# RFD900X_Holder.net
KiCad netlist of a schematic drawn in Altium Designer
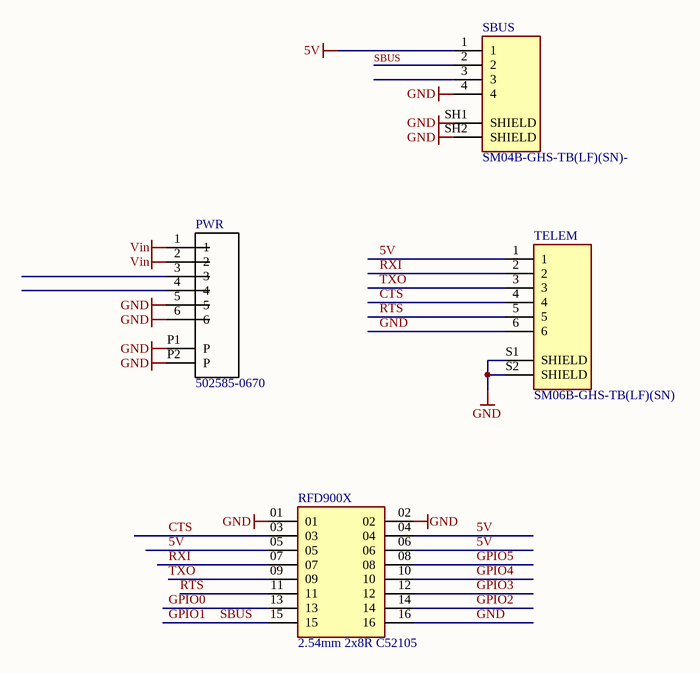
[diagram p0: RFD900X Holder.SchDoc]

(export (version "E")
  (design (tool "Eeschema 10.0.6"))
  (components
    (comp (ref "PWR")
      (value "502585-0670")
      (footprint "MOLEX_502585-0670")
      (fields (field (name "MF") "Molex"))
      (libsource (lib "lib") (part "502585-0670"))
    )
    (comp (ref "RFD900X")
      (value "2.54mm 2x8R C52105")
      (footprint "2.54mm 2x8R")
      (fields (field (name "MF") "BOOMELE") (field (name "MP") "C52105"))
      (libsource (lib "lib") (part "2.54mm 2x8R C52105"))
    )
    (comp (ref "SBUS")
      (value "SM04B-GHS-TB(LF)(SN)-")
      (footprint "JST_SM04B-GHS-TB(LF)(SN)-")
      (description "Connector Header Surface Mount, Right Angle 4 position 0.049 _1.25mm_")
      (fields (field (name "MP") "SM04B-GHS-TB(LF)(SN)") (field (name "MF") "JST Sales"))
      (libsource (lib "lib") (part "SM04B-GHS-TB(LF)(SN)-"))
    )
    (comp (ref "TELEM")
      (value "SM06B-GHS-TB(LF)(SN)")
      (footprint "JST_SM06B-GHS-TB(LF)(SN)")
      (description "Connector Header Surface Mount, Right Angle 6 position 0.049\" (1.25mm)")
      (fields (field (name "MP") "SM06B-GHS-TB_LF__SN_") (field (name "MF") "JST Sales"))
      (libsource (lib "lib") (part "SM06B-GHS-TB(LF)(SN)"))
    )
  )
  (nets
    (net (code "1") (name "/CTS") (class "Default")
      (node (ref "RFD900X") (pin "03") (pinfunction "03_03") (pintype "passive"))
      (node (ref "TELEM") (pin "4") (pinfunction "4_4") (pintype "passive"))
    )
    (net (code "2") (name "/GPIO0") (class "Default")
      (node (ref "RFD900X") (pin "13") (pinfunction "13_13") (pintype "passive"))
    )
    (net (code "3") (name "/GPIO1") (class "Default")
      (node (ref "RFD900X") (pin "15") (pinfunction "15_15") (pintype "passive"))
      (node (ref "SBUS") (pin "2") (pinfunction "2_2") (pintype "passive"))
    )
    (net (code "4") (name "/GPIO2") (class "Default")
      (node (ref "RFD900X") (pin "14") (pinfunction "14_14") (pintype "passive"))
    )
    (net (code "5") (name "/GPIO3") (class "Default")
      (node (ref "RFD900X") (pin "12") (pinfunction "12_12") (pintype "passive"))
    )
    (net (code "6") (name "/GPIO4") (class "Default")
      (node (ref "RFD900X") (pin "10") (pinfunction "10_10") (pintype "passive"))
    )
    (net (code "7") (name "/GPIO5") (class "Default")
      (node (ref "RFD900X") (pin "08") (pinfunction "08_08") (pintype "passive"))
    )
    (net (code "8") (name "/RTS") (class "Default")
      (node (ref "RFD900X") (pin "11") (pinfunction "11_11") (pintype "passive"))
      (node (ref "TELEM") (pin "5") (pinfunction "5_5") (pintype "passive"))
    )
    (net (code "9") (name "/RXI") (class "Default")
      (node (ref "RFD900X") (pin "07") (pinfunction "07_07") (pintype "passive"))
      (node (ref "TELEM") (pin "2") (pinfunction "2_2") (pintype "passive"))
    )
    (net (code "10") (name "/TXO") (class "Default")
      (node (ref "RFD900X") (pin "09") (pinfunction "09_09") (pintype "passive"))
      (node (ref "TELEM") (pin "3") (pinfunction "3_3") (pintype "passive"))
    )
    (net (code "11") (name "5V") (class "Default")
      (node (ref "RFD900X") (pin "04") (pinfunction "04_04") (pintype "passive"))
      (node (ref "RFD900X") (pin "05") (pinfunction "05_05") (pintype "passive"))
      (node (ref "RFD900X") (pin "06") (pinfunction "06_06") (pintype "passive"))
      (node (ref "SBUS") (pin "1") (pinfunction "1_1") (pintype "passive"))
      (node (ref "TELEM") (pin "1") (pinfunction "1_1") (pintype "passive"))
    )
    (net (code "12") (name "GND") (class "Default")
      (node (ref "PWR") (pin "5") (pinfunction "5_5") (pintype "passive"))
      (node (ref "PWR") (pin "6") (pinfunction "6_6") (pintype "passive"))
      (node (ref "PWR") (pin "P1") (pinfunction "P_P1") (pintype "passive"))
      (node (ref "PWR") (pin "P2") (pinfunction "P_P2") (pintype "passive"))
      (node (ref "RFD900X") (pin "01") (pinfunction "01_01") (pintype "passive"))
      (node (ref "RFD900X") (pin "02") (pinfunction "02_02") (pintype "passive"))
      (node (ref "RFD900X") (pin "16") (pinfunction "16_16") (pintype "passive"))
      (node (ref "SBUS") (pin "4") (pinfunction "4_4") (pintype "passive"))
      (node (ref "SBUS") (pin "SH1") (pinfunction "SHIELD_SH1") (pintype "power_in"))
      (node (ref "SBUS") (pin "SH2") (pinfunction "SHIELD_SH2") (pintype "power_in"))
      (node (ref "TELEM") (pin "6") (pinfunction "6_6") (pintype "passive"))
      (node (ref "TELEM") (pin "S1") (pinfunction "SHIELD_S1") (pintype "passive"))
      (node (ref "TELEM") (pin "S2") (pinfunction "SHIELD_S2") (pintype "passive"))
    )
    (net (code "13") (name "Vin") (class "Default")
      (node (ref "PWR") (pin "1") (pinfunction "1_1") (pintype "passive"))
      (node (ref "PWR") (pin "2") (pinfunction "2_2") (pintype "passive"))
    )
    (net (code "14") (name "unconnected-(PWR-Pad3)") (class "Default")
      (node (ref "PWR") (pin "3") (pinfunction "3_3") (pintype "passive"))
    )
    (net (code "15") (name "unconnected-(PWR-Pad4)") (class "Default")
      (node (ref "PWR") (pin "4") (pinfunction "4_4") (pintype "passive"))
    )
    (net (code "16") (name "unconnected-(SBUS-Pad3)") (class "Default")
      (node (ref "SBUS") (pin "3") (pinfunction "3_3") (pintype "passive"))
    )
  )
)
